# ATU_LC.net
KiCad netlist of a schematic drawn in Altium Designer
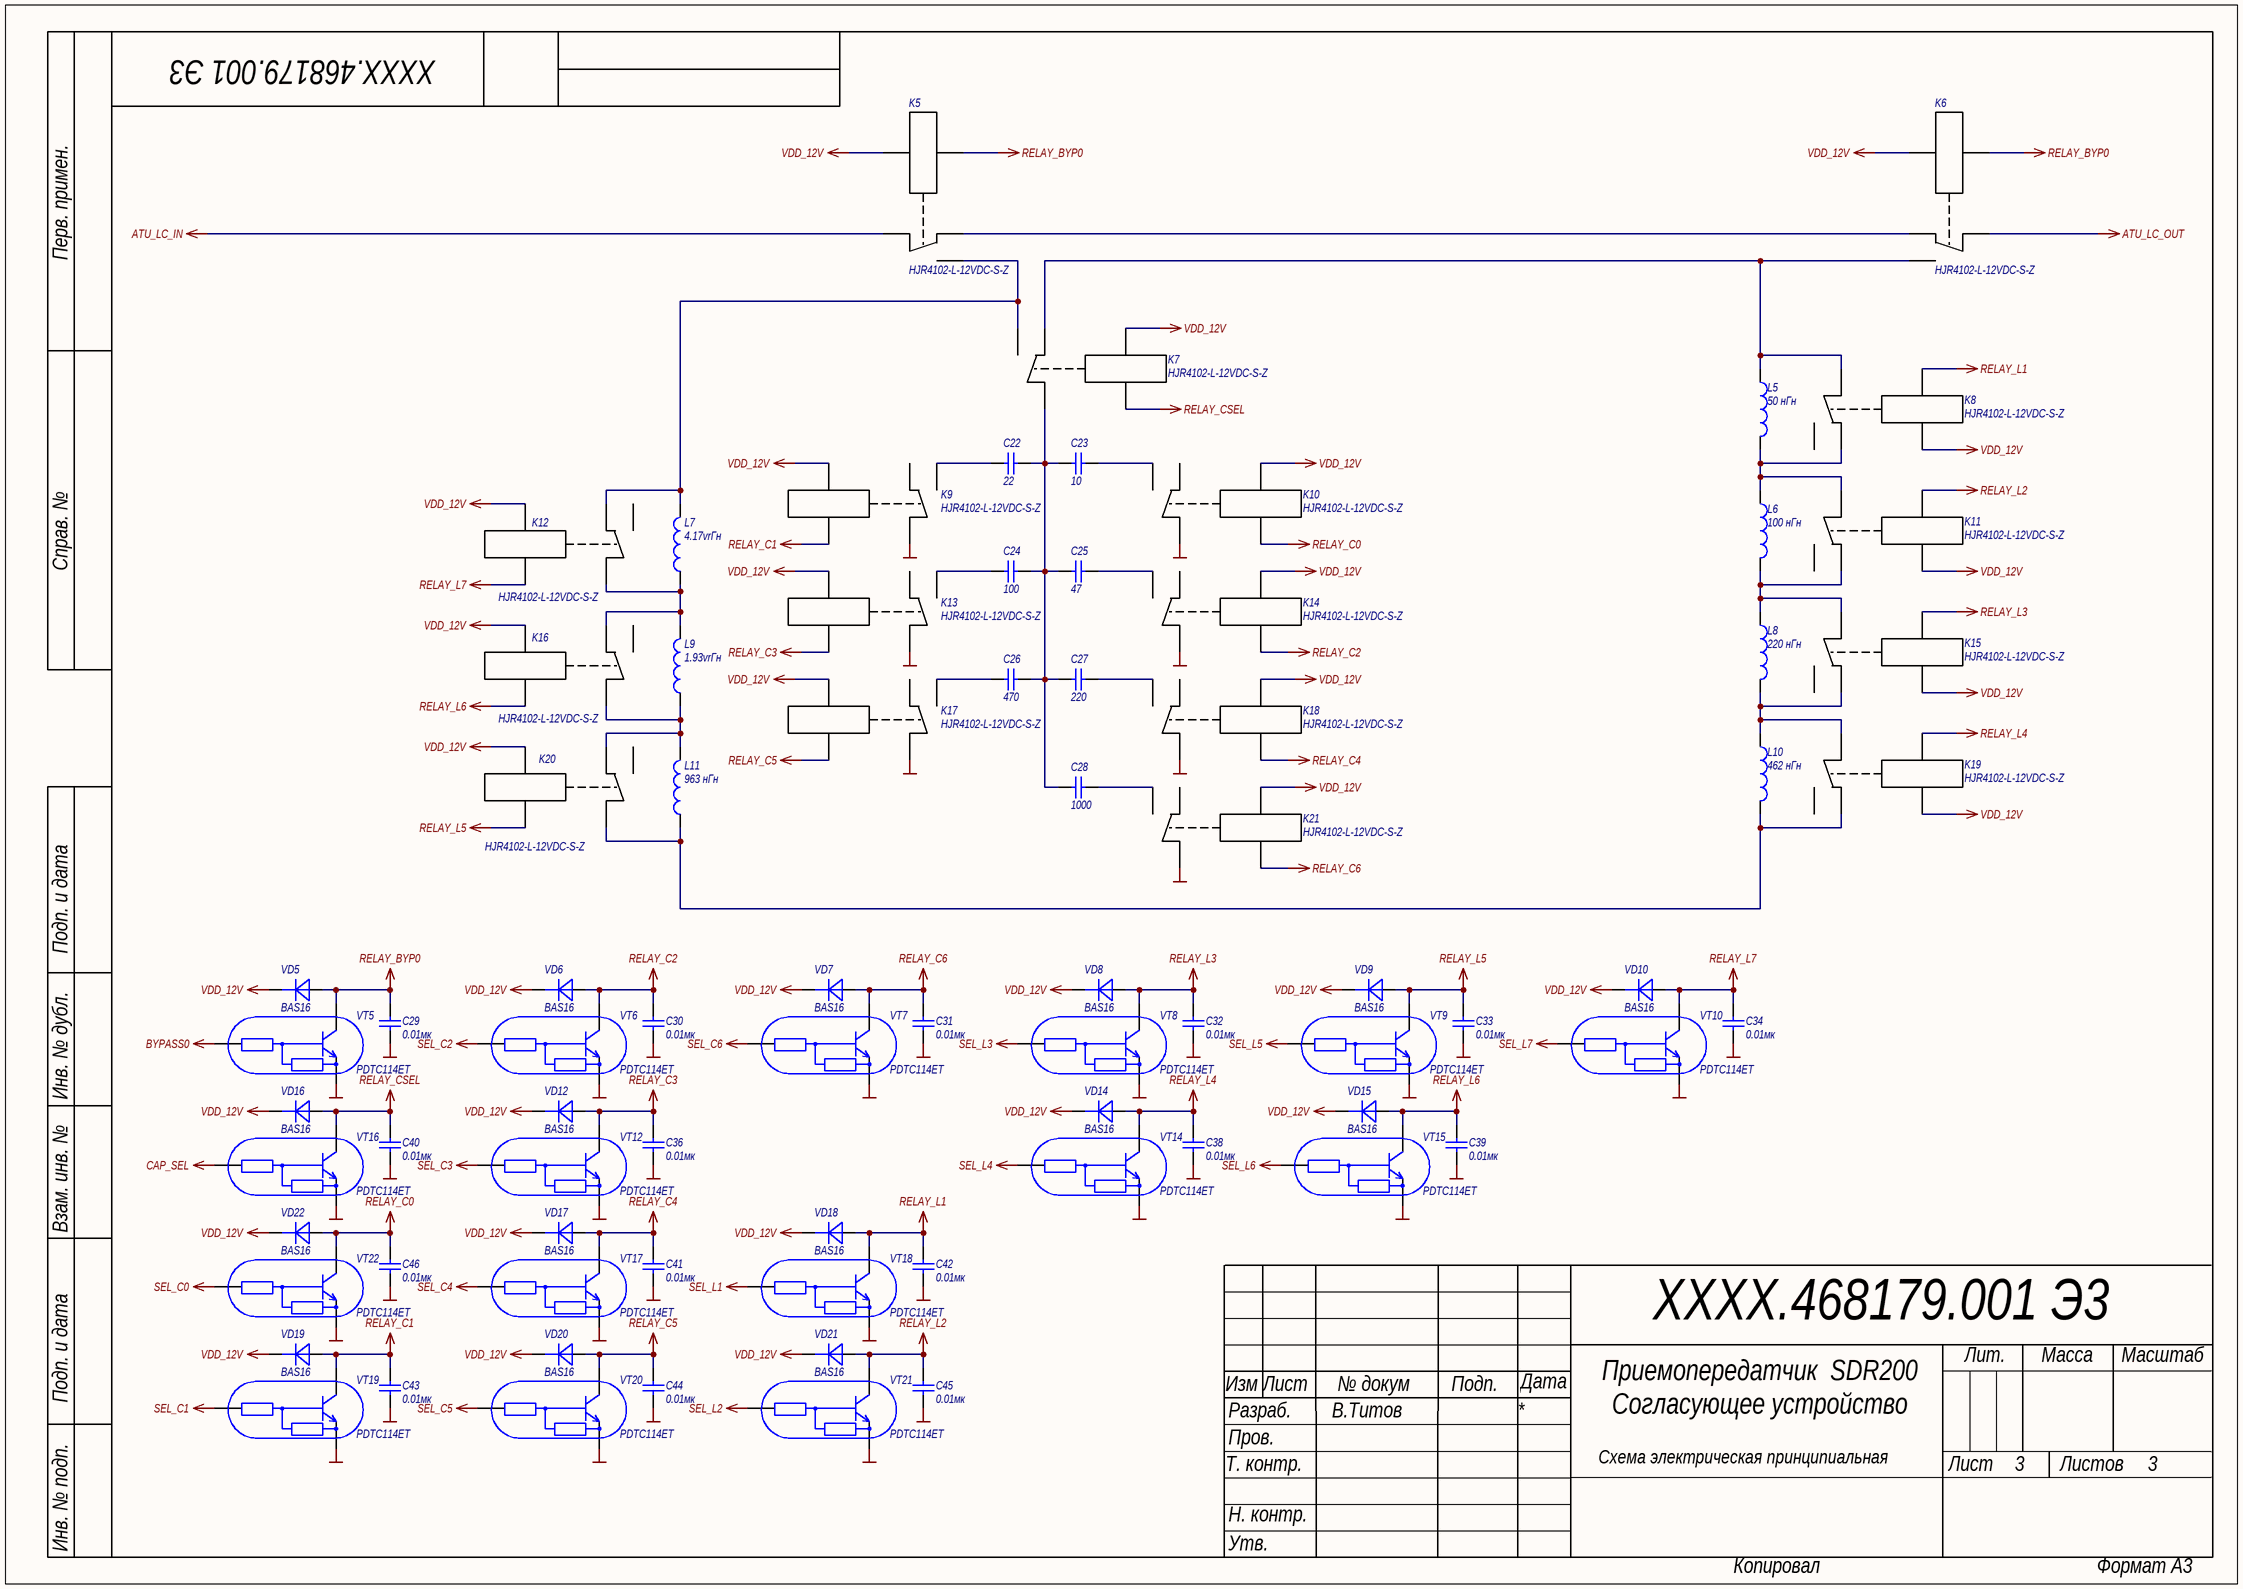
[diagram p0: ATU_LC.SchDoc]

(export (version "E")
  (design (tool "Eeschema 10.0.6"))
  (components
    (comp (ref "C22")
      (value "22")
      (footprint "CAPC3216X19L")
      (description "Кер. ЧИП-конденсатор")
      (fields (field (name "MANUFACTURER") "WALSIN") (field (name "TOLERANCE") "±5%"))
      (libsource (lib "nels_caps") (part "Кер.ЧИП конд. 1206 22пФ NP0 5% 2000В"))
    )
    (comp (ref "C23")
      (value "10")
      (footprint "CAPC3216X19L")
      (description "Кер. ЧИП-конденсатор")
      (fields (field (name "MANUFACTURER") "WALSIN") (field (name "TOLERANCE") "±5%"))
      (libsource (lib "nels_caps") (part "Кер.ЧИП конд. 1206 10пФ NP0 5% 2000В"))
    )
    (comp (ref "C24")
      (value "100")
      (footprint "CAPC3216X19L")
      (description "Кер. ЧИП-конденсатор")
      (fields (field (name "MANUFACTURER") "WALSIN") (field (name "TOLERANCE") "±5%"))
      (libsource (lib "nels_caps") (part "Кер.ЧИП конд. 1206 100пФ NP0 5% 2000В"))
    )
    (comp (ref "C25")
      (value "47")
      (footprint "CAPC3216X19L")
      (description "Кер. ЧИП-конденсатор")
      (fields (field (name "MANUFACTURER") "WALSIN") (field (name "TOLERANCE") "±5%"))
      (libsource (lib "nels_caps") (part "Кер.ЧИП конд. 1206 47пФ NP0 5% 2000В"))
    )
    (comp (ref "C26")
      (value "470")
      (footprint "CAPC3216X19L")
      (description "Кер. ЧИП-конденсатор")
      (fields (field (name "MANUFACTURER") "WALSIN") (field (name "TOLERANCE") "±10%"))
      (libsource (lib "nels_caps") (part "Кер.ЧИП конд. 1206 470пФ NP0 10% 2000В"))
    )
    (comp (ref "C27")
      (value "220")
      (footprint "CAPC3216X19L")
      (description "Кер. ЧИП-конденсатор")
      (fields (field (name "MANUFACTURER") "Johanson") (field (name "TOLERANCE") "±10%"))
      (libsource (lib "nels_caps") (part "Кер.ЧИП конд. 1206 220пФ NP0 5% 2000В"))
    )
    (comp (ref "C28")
      (value "1000")
      (footprint "CAPC3216X19L")
      (description "Кер. ЧИП-конденсатор")
      (fields (field (name "MANUFACTURER") "Johanson") (field (name "TOLERANCE") "±10%"))
      (libsource (lib "nels_caps") (part "Кер.ЧИП конд. 1206 1000пФ X7К 10% 2000В"))
    )
    (comp (ref "C29")
      (value "0.01мк")
      (footprint "CAPC1005X06N")
      (description "Кер. ЧИП-конденсатор")
      (fields (field (name "TOLERANCE") "±20%"))
      (libsource (lib "nels_caps") (part "Кер.ЧИП конд. 0402 0.01мкФ X7R 10%, 50В"))
    )
    (comp (ref "C30")
      (value "0.01мк")
      (footprint "CAPC1005X06N")
      (description "Кер. ЧИП-конденсатор")
      (fields (field (name "TOLERANCE") "±20%"))
      (libsource (lib "nels_caps") (part "Кер.ЧИП конд. 0402 0.01мкФ X7R 10%, 50В"))
    )
    (comp (ref "C31")
      (value "0.01мк")
      (footprint "CAPC1005X06N")
      (description "Кер. ЧИП-конденсатор")
      (fields (field (name "TOLERANCE") "±20%"))
      (libsource (lib "nels_caps") (part "Кер.ЧИП конд. 0402 0.01мкФ X7R 10%, 50В"))
    )
    (comp (ref "C32")
      (value "0.01мк")
      (footprint "CAPC1005X06N")
      (description "Кер. ЧИП-конденсатор")
      (fields (field (name "TOLERANCE") "±20%"))
      (libsource (lib "nels_caps") (part "Кер.ЧИП конд. 0402 0.01мкФ X7R 10%, 50В"))
    )
    (comp (ref "C33")
      (value "0.01мк")
      (footprint "CAPC1005X06N")
      (description "Кер. ЧИП-конденсатор")
      (fields (field (name "TOLERANCE") "±20%"))
      (libsource (lib "nels_caps") (part "Кер.ЧИП конд. 0402 0.01мкФ X7R 10%, 50В"))
    )
    (comp (ref "C34")
      (value "0.01мк")
      (footprint "CAPC1005X06N")
      (description "Кер. ЧИП-конденсатор")
      (fields (field (name "TOLERANCE") "±20%"))
      (libsource (lib "nels_caps") (part "Кер.ЧИП конд. 0402 0.01мкФ X7R 10%, 50В"))
    )
    (comp (ref "C36")
      (value "0.01мк")
      (footprint "CAPC1005X06N")
      (description "Кер. ЧИП-конденсатор")
      (fields (field (name "TOLERANCE") "±20%"))
      (libsource (lib "nels_caps") (part "Кер.ЧИП конд. 0402 0.01мкФ X7R 10%, 50В"))
    )
    (comp (ref "C38")
      (value "0.01мк")
      (footprint "CAPC1005X06N")
      (description "Кер. ЧИП-конденсатор")
      (fields (field (name "TOLERANCE") "±20%"))
      (libsource (lib "nels_caps") (part "Кер.ЧИП конд. 0402 0.01мкФ X7R 10%, 50В"))
    )
    (comp (ref "C39")
      (value "0.01мк")
      (footprint "CAPC1005X06N")
      (description "Кер. ЧИП-конденсатор")
      (fields (field (name "TOLERANCE") "±20%"))
      (libsource (lib "nels_caps") (part "Кер.ЧИП конд. 0402 0.01мкФ X7R 10%, 50В"))
    )
    (comp (ref "C40")
      (value "0.01мк")
      (footprint "CAPC1005X06N")
      (description "Кер. ЧИП-конденсатор")
      (fields (field (name "TOLERANCE") "±20%"))
      (libsource (lib "nels_caps") (part "Кер.ЧИП конд. 0402 0.01мкФ X7R 10%, 50В"))
    )
    (comp (ref "C41")
      (value "0.01мк")
      (footprint "CAPC1005X06N")
      (description "Кер. ЧИП-конденсатор")
      (fields (field (name "TOLERANCE") "±20%"))
      (libsource (lib "nels_caps") (part "Кер.ЧИП конд. 0402 0.01мкФ X7R 10%, 50В"))
    )
    (comp (ref "C42")
      (value "0.01мк")
      (footprint "CAPC1005X06N")
      (description "Кер. ЧИП-конденсатор")
      (fields (field (name "TOLERANCE") "±20%"))
      (libsource (lib "nels_caps") (part "Кер.ЧИП конд. 0402 0.01мкФ X7R 10%, 50В"))
    )
    (comp (ref "C43")
      (value "0.01мк")
      (footprint "CAPC1005X06N")
      (description "Кер. ЧИП-конденсатор")
      (fields (field (name "TOLERANCE") "±20%"))
      (libsource (lib "nels_caps") (part "Кер.ЧИП конд. 0402 0.01мкФ X7R 10%, 50В"))
    )
    (comp (ref "C44")
      (value "0.01мк")
      (footprint "CAPC1005X06N")
      (description "Кер. ЧИП-конденсатор")
      (fields (field (name "TOLERANCE") "±20%"))
      (libsource (lib "nels_caps") (part "Кер.ЧИП конд. 0402 0.01мкФ X7R 10%, 50В"))
    )
    (comp (ref "C45")
      (value "0.01мк")
      (footprint "CAPC1005X06N")
      (description "Кер. ЧИП-конденсатор")
      (fields (field (name "TOLERANCE") "±20%"))
      (libsource (lib "nels_caps") (part "Кер.ЧИП конд. 0402 0.01мкФ X7R 10%, 50В"))
    )
    (comp (ref "C46")
      (value "0.01мк")
      (footprint "CAPC1005X06N")
      (description "Кер. ЧИП-конденсатор")
      (fields (field (name "TOLERANCE") "±20%"))
      (libsource (lib "nels_caps") (part "Кер.ЧИП конд. 0402 0.01мкФ X7R 10%, 50В"))
    )
    (comp (ref "K5")
      (value "HJR4102-L-12VDC-S-Z")
      (footprint "HJR4102")
      (description "Реле 1пер. 12VDC, 1A/240VAC")
      (libsource (lib "nels_other") (part "Реле HJR4102-L-12VDC-S-Z"))
    )
    (comp (ref "K6")
      (value "HJR4102-L-12VDC-S-Z")
      (footprint "HJR4102")
      (description "Реле 1пер. 12VDC, 1A/240VAC")
      (libsource (lib "nels_other") (part "Реле HJR4102-L-12VDC-S-Z"))
    )
    (comp (ref "K7")
      (value "HJR4102-L-12VDC-S-Z")
      (footprint "HJR4102")
      (description "Реле 1пер. 12VDC, 1A/240VAC")
      (libsource (lib "nels_other") (part "Реле HJR4102-L-12VDC-S-Z"))
    )
    (comp (ref "K8")
      (value "HJR4102-L-12VDC-S-Z")
      (footprint "HJR4102")
      (description "Реле 1пер. 12VDC, 1A/240VAC")
      (libsource (lib "nels_other") (part "Реле HJR4102-L-12VDC-S-Z"))
    )
    (comp (ref "K9")
      (value "HJR4102-L-12VDC-S-Z")
      (footprint "HJR4102")
      (description "Реле 1пер. 12VDC, 1A/240VAC")
      (libsource (lib "nels_other") (part "Реле HJR4102-L-12VDC-S-Z"))
    )
    (comp (ref "K10")
      (value "HJR4102-L-12VDC-S-Z")
      (footprint "HJR4102")
      (description "Реле 1пер. 12VDC, 1A/240VAC")
      (libsource (lib "nels_other") (part "Реле HJR4102-L-12VDC-S-Z"))
    )
    (comp (ref "K11")
      (value "HJR4102-L-12VDC-S-Z")
      (footprint "HJR4102")
      (description "Реле 1пер. 12VDC, 1A/240VAC")
      (libsource (lib "nels_other") (part "Реле HJR4102-L-12VDC-S-Z"))
    )
    (comp (ref "K12")
      (value "HJR4102-L-12VDC-S-Z")
      (footprint "HJR4102")
      (description "Реле 1пер. 12VDC, 1A/240VAC")
      (libsource (lib "nels_other") (part "Реле HJR4102-L-12VDC-S-Z"))
    )
    (comp (ref "K13")
      (value "HJR4102-L-12VDC-S-Z")
      (footprint "HJR4102")
      (description "Реле 1пер. 12VDC, 1A/240VAC")
      (libsource (lib "nels_other") (part "Реле HJR4102-L-12VDC-S-Z"))
    )
    (comp (ref "K14")
      (value "HJR4102-L-12VDC-S-Z")
      (footprint "HJR4102")
      (description "Реле 1пер. 12VDC, 1A/240VAC")
      (libsource (lib "nels_other") (part "Реле HJR4102-L-12VDC-S-Z"))
    )
    (comp (ref "K15")
      (value "HJR4102-L-12VDC-S-Z")
      (footprint "HJR4102")
      (description "Реле 1пер. 12VDC, 1A/240VAC")
      (libsource (lib "nels_other") (part "Реле HJR4102-L-12VDC-S-Z"))
    )
    (comp (ref "K16")
      (value "HJR4102-L-12VDC-S-Z")
      (footprint "HJR4102")
      (description "Реле 1пер. 12VDC, 1A/240VAC")
      (libsource (lib "nels_other") (part "Реле HJR4102-L-12VDC-S-Z"))
    )
    (comp (ref "K17")
      (value "HJR4102-L-12VDC-S-Z")
      (footprint "HJR4102")
      (description "Реле 1пер. 12VDC, 1A/240VAC")
      (libsource (lib "nels_other") (part "Реле HJR4102-L-12VDC-S-Z"))
    )
    (comp (ref "K18")
      (value "HJR4102-L-12VDC-S-Z")
      (footprint "HJR4102")
      (description "Реле 1пер. 12VDC, 1A/240VAC")
      (libsource (lib "nels_other") (part "Реле HJR4102-L-12VDC-S-Z"))
    )
    (comp (ref "K19")
      (value "HJR4102-L-12VDC-S-Z")
      (footprint "HJR4102")
      (description "Реле 1пер. 12VDC, 1A/240VAC")
      (libsource (lib "nels_other") (part "Реле HJR4102-L-12VDC-S-Z"))
    )
    (comp (ref "K20")
      (value "HJR4102-L-12VDC-S-Z")
      (footprint "HJR4102")
      (description "Реле 1пер. 12VDC, 1A/240VAC")
      (libsource (lib "nels_other") (part "Реле HJR4102-L-12VDC-S-Z"))
    )
    (comp (ref "K21")
      (value "HJR4102-L-12VDC-S-Z")
      (footprint "HJR4102")
      (description "Реле 1пер. 12VDC, 1A/240VAC")
      (libsource (lib "nels_other") (part "Реле HJR4102-L-12VDC-S-Z"))
    )
    (comp (ref "L5")
      (value "50 нГн")
      (footprint "COIL D4 W3 L3")
      (description "3 витка, диаметр 4мм, длина 3мм, провод 0,5мм")
      (libsource (lib "nels_ind") (part "Индуктивность 50 нГн"))
    )
    (comp (ref "L6")
      (value "100 нГн")
      (footprint "COIL D6.4 W4 L3.5")
      (description "4 витка, диаметр 6мм, длина 3.5мм, провод 0.8мм")
      (libsource (lib "nels_ind") (part "Индуктивность  100 нГн"))
    )
    (comp (ref "L7")
      (value "4.17vrГн")
      (footprint "T68-2x2")
      (description "13 витков на 2 кольцах")
      (libsource (lib "nels_ind") (part "Индуктивность 2XT68-2 4.17vrГн"))
    )
    (comp (ref "L8")
      (value "220 нГн")
      (footprint "COIL D6.4 W7 L6")
      (description "7 витков, диаметр 6мм, длина 6мм, провод 0.8мм")
      (libsource (lib "nels_ind") (part "Индуктивность 220 нГн"))
    )
    (comp (ref "L9")
      (value "1.93vrГн")
      (footprint "T68-2x2")
      (description "13 витков на 2 кольцах")
      (libsource (lib "nels_ind") (part "Индуктивность 2XT68-2 1.93vrГн"))
    )
    (comp (ref "L10")
      (value "462 нГн")
      (footprint "T68-2")
      (description "9 витков")
      (libsource (lib "nels_ind") (part "Индуктивность T68-2 462 нГн"))
    )
    (comp (ref "L11")
      (value "963 нГн")
      (footprint "T68-2")
      (description "13 витков")
      (libsource (lib "nels_ind") (part "Индуктивность T68-2 963 нГн"))
    )
    (comp (ref "VD5")
      (value "BAS16")
      (footprint "SOT23_N")
      (description "High-speed switching diodes")
      (fields (field (name "MANUFACTURER") "Nexperia"))
      (libsource (lib "nels_other") (part "ЧИП диод BAS16"))
    )
    (comp (ref "VD6")
      (value "BAS16")
      (footprint "SOT23_N")
      (description "High-speed switching diodes")
      (fields (field (name "MANUFACTURER") "Nexperia"))
      (libsource (lib "nels_other") (part "ЧИП диод BAS16"))
    )
    (comp (ref "VD7")
      (value "BAS16")
      (footprint "SOT23_N")
      (description "High-speed switching diodes")
      (fields (field (name "MANUFACTURER") "Nexperia"))
      (libsource (lib "nels_other") (part "ЧИП диод BAS16"))
    )
    (comp (ref "VD8")
      (value "BAS16")
      (footprint "SOT23_N")
      (description "High-speed switching diodes")
      (fields (field (name "MANUFACTURER") "Nexperia"))
      (libsource (lib "nels_other") (part "ЧИП диод BAS16"))
    )
    (comp (ref "VD9")
      (value "BAS16")
      (footprint "SOT23_N")
      (description "High-speed switching diodes")
      (fields (field (name "MANUFACTURER") "Nexperia"))
      (libsource (lib "nels_other") (part "ЧИП диод BAS16"))
    )
    (comp (ref "VD10")
      (value "BAS16")
      (footprint "SOT23_N")
      (description "High-speed switching diodes")
      (fields (field (name "MANUFACTURER") "Nexperia"))
      (libsource (lib "nels_other") (part "ЧИП диод BAS16"))
    )
    (comp (ref "VD12")
      (value "BAS16")
      (footprint "SOT23_N")
      (description "High-speed switching diodes")
      (fields (field (name "MANUFACTURER") "Nexperia"))
      (libsource (lib "nels_other") (part "ЧИП диод BAS16"))
    )
    (comp (ref "VD14")
      (value "BAS16")
      (footprint "SOT23_N")
      (description "High-speed switching diodes")
      (fields (field (name "MANUFACTURER") "Nexperia"))
      (libsource (lib "nels_other") (part "ЧИП диод BAS16"))
    )
    (comp (ref "VD15")
      (value "BAS16")
      (footprint "SOT23_N")
      (description "High-speed switching diodes")
      (fields (field (name "MANUFACTURER") "Nexperia"))
      (libsource (lib "nels_other") (part "ЧИП диод BAS16"))
    )
    (comp (ref "VD16")
      (value "BAS16")
      (footprint "SOT23_N")
      (description "High-speed switching diodes")
      (fields (field (name "MANUFACTURER") "Nexperia"))
      (libsource (lib "nels_other") (part "ЧИП диод BAS16"))
    )
    (comp (ref "VD17")
      (value "BAS16")
      (footprint "SOT23_N")
      (description "High-speed switching diodes")
      (fields (field (name "MANUFACTURER") "Nexperia"))
      (libsource (lib "nels_other") (part "ЧИП диод BAS16"))
    )
    (comp (ref "VD18")
      (value "BAS16")
      (footprint "SOT23_N")
      (description "High-speed switching diodes")
      (fields (field (name "MANUFACTURER") "Nexperia"))
      (libsource (lib "nels_other") (part "ЧИП диод BAS16"))
    )
    (comp (ref "VD19")
      (value "BAS16")
      (footprint "SOT23_N")
      (description "High-speed switching diodes")
      (fields (field (name "MANUFACTURER") "Nexperia"))
      (libsource (lib "nels_other") (part "ЧИП диод BAS16"))
    )
    (comp (ref "VD20")
      (value "BAS16")
      (footprint "SOT23_N")
      (description "High-speed switching diodes")
      (fields (field (name "MANUFACTURER") "Nexperia"))
      (libsource (lib "nels_other") (part "ЧИП диод BAS16"))
    )
    (comp (ref "VD21")
      (value "BAS16")
      (footprint "SOT23_N")
      (description "High-speed switching diodes")
      (fields (field (name "MANUFACTURER") "Nexperia"))
      (libsource (lib "nels_other") (part "ЧИП диод BAS16"))
    )
    (comp (ref "VD22")
      (value "BAS16")
      (footprint "SOT23_N")
      (description "High-speed switching diodes")
      (fields (field (name "MANUFACTURER") "Nexperia"))
      (libsource (lib "nels_other") (part "ЧИП диод BAS16"))
    )
    (comp (ref "VT5")
      (value "PDTC114ET")
      (footprint "SOT23_N")
      (description "NPN resistor-equipped transistors;  R1 = 10 k, R2 = 10")
      (libsource (lib "nels_other") (part "ЧИП транзистор PDTC114ET"))
    )
    (comp (ref "VT6")
      (value "PDTC114ET")
      (footprint "SOT23_N")
      (description "NPN resistor-equipped transistors;  R1 = 10 k, R2 = 10")
      (libsource (lib "nels_other") (part "ЧИП транзистор PDTC114ET"))
    )
    (comp (ref "VT7")
      (value "PDTC114ET")
      (footprint "SOT23_N")
      (description "NPN resistor-equipped transistors;  R1 = 10 k, R2 = 10")
      (libsource (lib "nels_other") (part "ЧИП транзистор PDTC114ET"))
    )
    (comp (ref "VT8")
      (value "PDTC114ET")
      (footprint "SOT23_N")
      (description "NPN resistor-equipped transistors;  R1 = 10 k, R2 = 10")
      (libsource (lib "nels_other") (part "ЧИП транзистор PDTC114ET"))
    )
    (comp (ref "VT9")
      (value "PDTC114ET")
      (footprint "SOT23_N")
      (description "NPN resistor-equipped transistors;  R1 = 10 k, R2 = 10")
      (libsource (lib "nels_other") (part "ЧИП транзистор PDTC114ET"))
    )
    (comp (ref "VT10")
      (value "PDTC114ET")
      (footprint "SOT23_N")
      (description "NPN resistor-equipped transistors;  R1 = 10 k, R2 = 10")
      (libsource (lib "nels_other") (part "ЧИП транзистор PDTC114ET"))
    )
    (comp (ref "VT12")
      (value "PDTC114ET")
      (footprint "SOT23_N")
      (description "NPN resistor-equipped transistors;  R1 = 10 k, R2 = 10")
      (libsource (lib "nels_other") (part "ЧИП транзистор PDTC114ET"))
    )
    (comp (ref "VT14")
      (value "PDTC114ET")
      (footprint "SOT23_N")
      (description "NPN resistor-equipped transistors;  R1 = 10 k, R2 = 10")
      (libsource (lib "nels_other") (part "ЧИП транзистор PDTC114ET"))
    )
    (comp (ref "VT15")
      (value "PDTC114ET")
      (footprint "SOT23_N")
      (description "NPN resistor-equipped transistors;  R1 = 10 k, R2 = 10")
      (libsource (lib "nels_other") (part "ЧИП транзистор PDTC114ET"))
    )
    (comp (ref "VT16")
      (value "PDTC114ET")
      (footprint "SOT23_N")
      (description "NPN resistor-equipped transistors;  R1 = 10 k, R2 = 10")
      (libsource (lib "nels_other") (part "ЧИП транзистор PDTC114ET"))
    )
    (comp (ref "VT17")
      (value "PDTC114ET")
      (footprint "SOT23_N")
      (description "NPN resistor-equipped transistors;  R1 = 10 k, R2 = 10")
      (libsource (lib "nels_other") (part "ЧИП транзистор PDTC114ET"))
    )
    (comp (ref "VT18")
      (value "PDTC114ET")
      (footprint "SOT23_N")
      (description "NPN resistor-equipped transistors;  R1 = 10 k, R2 = 10")
      (libsource (lib "nels_other") (part "ЧИП транзистор PDTC114ET"))
    )
    (comp (ref "VT19")
      (value "PDTC114ET")
      (footprint "SOT23_N")
      (description "NPN resistor-equipped transistors;  R1 = 10 k, R2 = 10")
      (libsource (lib "nels_other") (part "ЧИП транзистор PDTC114ET"))
    )
    (comp (ref "VT20")
      (value "PDTC114ET")
      (footprint "SOT23_N")
      (description "NPN resistor-equipped transistors;  R1 = 10 k, R2 = 10")
      (libsource (lib "nels_other") (part "ЧИП транзистор PDTC114ET"))
    )
    (comp (ref "VT21")
      (value "PDTC114ET")
      (footprint "SOT23_N")
      (description "NPN resistor-equipped transistors;  R1 = 10 k, R2 = 10")
      (libsource (lib "nels_other") (part "ЧИП транзистор PDTC114ET"))
    )
    (comp (ref "VT22")
      (value "PDTC114ET")
      (footprint "SOT23_N")
      (description "NPN resistor-equipped transistors;  R1 = 10 k, R2 = 10")
      (libsource (lib "nels_other") (part "ЧИП транзистор PDTC114ET"))
    )
  )
  (nets
    (net (code "1") (name "ATU_LC_IN") (class "Default") (node (ref "K5") (pin "1") (pintype "passive")))
    (net (code "2") (name "ATU_LC_OUT") (class "Default") (node (ref "K6") (pin "1") (pintype "passive")))
    (net (code "3") (name "BYPASS0") (class "Default")
      (node (ref "VT5") (pin "1") (pinfunction "B_1") (pintype "passive"))
    )
    (net (code "4") (name "CAP_SEL") (class "Default")
      (node (ref "VT16") (pin "1") (pinfunction "B_1") (pintype "passive"))
    )
    (net (code "5") (name "GND") (class "Default")
      (node (ref "C29") (pin "1") (pinfunction "1_1") (pintype "passive"))
      (node (ref "C30") (pin "1") (pinfunction "1_1") (pintype "passive"))
      (node (ref "C31") (pin "1") (pinfunction "1_1") (pintype "passive"))
      (node (ref "C32") (pin "1") (pinfunction "1_1") (pintype "passive"))
      (node (ref "C33") (pin "1") (pinfunction "1_1") (pintype "passive"))
      (node (ref "C34") (pin "1") (pinfunction "1_1") (pintype "passive"))
      (node (ref "C36") (pin "1") (pinfunction "1_1") (pintype "passive"))
      (node (ref "C38") (pin "1") (pinfunction "1_1") (pintype "passive"))
      (node (ref "C39") (pin "1") (pinfunction "1_1") (pintype "passive"))
      (node (ref "C40") (pin "1") (pinfunction "1_1") (pintype "passive"))
      (node (ref "C41") (pin "1") (pinfunction "1_1") (pintype "passive"))
      (node (ref "C42") (pin "1") (pinfunction "1_1") (pintype "passive"))
      (node (ref "C43") (pin "1") (pinfunction "1_1") (pintype "passive"))
      (node (ref "C44") (pin "1") (pinfunction "1_1") (pintype "passive"))
      (node (ref "C45") (pin "1") (pinfunction "1_1") (pintype "passive"))
      (node (ref "C46") (pin "1") (pinfunction "1_1") (pintype "passive"))
      (node (ref "K10") (pin "1") (pintype "passive"))
      (node (ref "K13") (pin "1") (pintype "passive"))
      (node (ref "K14") (pin "1") (pintype "passive"))
      (node (ref "K17") (pin "1") (pintype "passive"))
      (node (ref "K18") (pin "1") (pintype "passive"))
      (node (ref "K21") (pin "1") (pintype "passive"))
      (node (ref "K9") (pin "1") (pintype "passive"))
      (node (ref "VT10") (pin "2") (pinfunction "E_2") (pintype "passive"))
      (node (ref "VT12") (pin "2") (pinfunction "E_2") (pintype "passive"))
      (node (ref "VT14") (pin "2") (pinfunction "E_2") (pintype "passive"))
      (node (ref "VT15") (pin "2") (pinfunction "E_2") (pintype "passive"))
      (node (ref "VT16") (pin "2") (pinfunction "E_2") (pintype "passive"))
      (node (ref "VT17") (pin "2") (pinfunction "E_2") (pintype "passive"))
      (node (ref "VT18") (pin "2") (pinfunction "E_2") (pintype "passive"))
      (node (ref "VT19") (pin "2") (pinfunction "E_2") (pintype "passive"))
      (node (ref "VT20") (pin "2") (pinfunction "E_2") (pintype "passive"))
      (node (ref "VT21") (pin "2") (pinfunction "E_2") (pintype "passive"))
      (node (ref "VT22") (pin "2") (pinfunction "E_2") (pintype "passive"))
      (node (ref "VT5") (pin "2") (pinfunction "E_2") (pintype "passive"))
      (node (ref "VT6") (pin "2") (pinfunction "E_2") (pintype "passive"))
      (node (ref "VT7") (pin "2") (pinfunction "E_2") (pintype "passive"))
      (node (ref "VT8") (pin "2") (pinfunction "E_2") (pintype "passive"))
      (node (ref "VT9") (pin "2") (pinfunction "E_2") (pintype "passive"))
    )
    (net (code "6") (name "Net-(C22-Pad1)") (class "Default")
      (node (ref "C22") (pin "1") (pinfunction "1_1") (pintype "passive"))
      (node (ref "C23") (pin "2") (pinfunction "2_2") (pintype "passive"))
      (node (ref "C24") (pin "1") (pinfunction "1_1") (pintype "passive"))
      (node (ref "C25") (pin "2") (pinfunction "2_2") (pintype "passive"))
      (node (ref "C26") (pin "1") (pinfunction "1_1") (pintype "passive"))
      (node (ref "C27") (pin "2") (pinfunction "2_2") (pintype "passive"))
      (node (ref "C28") (pin "2") (pinfunction "2_2") (pintype "passive"))
      (node (ref "K7") (pin "1") (pintype "passive"))
    )
    (net (code "7") (name "Net-(C22-Pad2)") (class "Default")
      (node (ref "C22") (pin "2") (pinfunction "2_2") (pintype "passive"))
      (node (ref "K9") (pin "6") (pintype "passive"))
    )
    (net (code "8") (name "Net-(C23-Pad1)") (class "Default")
      (node (ref "C23") (pin "1") (pinfunction "1_1") (pintype "passive"))
      (node (ref "K10") (pin "6") (pintype "passive"))
    )
    (net (code "9") (name "Net-(C24-Pad2)") (class "Default")
      (node (ref "C24") (pin "2") (pinfunction "2_2") (pintype "passive"))
      (node (ref "K13") (pin "6") (pintype "passive"))
    )
    (net (code "10") (name "Net-(C25-Pad1)") (class "Default")
      (node (ref "C25") (pin "1") (pinfunction "1_1") (pintype "passive"))
      (node (ref "K14") (pin "6") (pintype "passive"))
    )
    (net (code "11") (name "Net-(C26-Pad2)") (class "Default")
      (node (ref "C26") (pin "2") (pinfunction "2_2") (pintype "passive"))
      (node (ref "K17") (pin "6") (pintype "passive"))
    )
    (net (code "12") (name "Net-(C27-Pad1)") (class "Default")
      (node (ref "C27") (pin "1") (pinfunction "1_1") (pintype "passive"))
      (node (ref "K18") (pin "6") (pintype "passive"))
    )
    (net (code "13") (name "Net-(C28-Pad1)") (class "Default")
      (node (ref "C28") (pin "1") (pinfunction "1_1") (pintype "passive"))
      (node (ref "K21") (pin "6") (pintype "passive"))
    )
    (net (code "14") (name "Net-(K5-Pad7)") (class "Default")
      (node (ref "K5") (pin "7") (pintype "passive"))
      (node (ref "K6") (pin "7") (pintype "passive"))
    )
    (net (code "15") (name "Net-(K6-Pad6)") (class "Default")
      (node (ref "K6") (pin "6") (pintype "passive"))
      (node (ref "K7") (pin "7") (pintype "passive"))
      (node (ref "K8") (pin "1") (pintype "passive"))
      (node (ref "L5") (pin "1") (pinfunction "1_1") (pintype "passive"))
    )
    (net (code "16") (name "Net-(K11-Pad1)") (class "Default")
      (node (ref "K11") (pin "1") (pintype "passive"))
      (node (ref "K8") (pin "7") (pintype "passive"))
      (node (ref "L5") (pin "2") (pinfunction "2_2") (pintype "passive"))
      (node (ref "L6") (pin "1") (pinfunction "1_1") (pintype "passive"))
    )
    (net (code "17") (name "Net-(K11-Pad7)") (class "Default")
      (node (ref "K11") (pin "7") (pintype "passive"))
      (node (ref "K15") (pin "1") (pintype "passive"))
      (node (ref "L6") (pin "2") (pinfunction "2_2") (pintype "passive"))
      (node (ref "L8") (pin "1") (pinfunction "1_1") (pintype "passive"))
    )
    (net (code "18") (name "Net-(K12-Pad1)") (class "Default")
      (node (ref "K12") (pin "1") (pintype "passive"))
      (node (ref "K16") (pin "7") (pintype "passive"))
      (node (ref "L7") (pin "1") (pinfunction "1_1") (pintype "passive"))
      (node (ref "L9") (pin "2") (pinfunction "2_2") (pintype "passive"))
    )
    (net (code "19") (name "Net-(K12-Pad7)") (class "Default")
      (node (ref "K12") (pin "7") (pintype "passive"))
      (node (ref "K5") (pin "6") (pintype "passive"))
      (node (ref "K7") (pin "6") (pintype "passive"))
      (node (ref "L7") (pin "2") (pinfunction "2_2") (pintype "passive"))
    )
    (net (code "20") (name "Net-(K15-Pad7)") (class "Default")
      (node (ref "K15") (pin "7") (pintype "passive"))
      (node (ref "K19") (pin "1") (pintype "passive"))
      (node (ref "L10") (pin "1") (pinfunction "1_1") (pintype "passive"))
      (node (ref "L8") (pin "2") (pinfunction "2_2") (pintype "passive"))
    )
    (net (code "21") (name "Net-(K16-Pad1)") (class "Default")
      (node (ref "K16") (pin "1") (pintype "passive"))
      (node (ref "K20") (pin "7") (pintype "passive"))
      (node (ref "L11") (pin "2") (pinfunction "2_2") (pintype "passive"))
      (node (ref "L9") (pin "1") (pinfunction "1_1") (pintype "passive"))
    )
    (net (code "22") (name "Net-(K19-Pad7)") (class "Default")
      (node (ref "K19") (pin "7") (pintype "passive"))
      (node (ref "K20") (pin "1") (pintype "passive"))
      (node (ref "L10") (pin "2") (pinfunction "2_2") (pintype "passive"))
      (node (ref "L11") (pin "1") (pinfunction "1_1") (pintype "passive"))
    )
    (net (code "23") (name "RELAY_BYP0") (class "Default")
      (node (ref "C29") (pin "2") (pinfunction "2_2") (pintype "passive"))
      (node (ref "K5") (pin "5") (pintype "passive"))
      (node (ref "K6") (pin "8") (pintype "passive"))
      (node (ref "VD5") (pin "1") (pinfunction "A_1") (pintype "passive"))
      (node (ref "VT5") (pin "3") (pinfunction "C_3") (pintype "passive"))
    )
    (net (code "24") (name "RELAY_C0") (class "Default")
      (node (ref "C46") (pin "2") (pinfunction "2_2") (pintype "passive"))
      (node (ref "K10") (pin "8") (pintype "passive"))
      (node (ref "VD22") (pin "1") (pinfunction "A_1") (pintype "passive"))
      (node (ref "VT22") (pin "3") (pinfunction "C_3") (pintype "passive"))
    )
    (net (code "25") (name "RELAY_C1") (class "Default")
      (node (ref "C43") (pin "2") (pinfunction "2_2") (pintype "passive"))
      (node (ref "K9") (pin "8") (pintype "passive"))
      (node (ref "VD19") (pin "1") (pinfunction "A_1") (pintype "passive"))
      (node (ref "VT19") (pin "3") (pinfunction "C_3") (pintype "passive"))
    )
    (net (code "26") (name "RELAY_C2") (class "Default")
      (node (ref "C30") (pin "2") (pinfunction "2_2") (pintype "passive"))
      (node (ref "K14") (pin "8") (pintype "passive"))
      (node (ref "VD6") (pin "1") (pinfunction "A_1") (pintype "passive"))
      (node (ref "VT6") (pin "3") (pinfunction "C_3") (pintype "passive"))
    )
    (net (code "27") (name "RELAY_C3") (class "Default")
      (node (ref "C36") (pin "2") (pinfunction "2_2") (pintype "passive"))
      (node (ref "K13") (pin "8") (pintype "passive"))
      (node (ref "VD12") (pin "1") (pinfunction "A_1") (pintype "passive"))
      (node (ref "VT12") (pin "3") (pinfunction "C_3") (pintype "passive"))
    )
    (net (code "28") (name "RELAY_C4") (class "Default")
      (node (ref "C41") (pin "2") (pinfunction "2_2") (pintype "passive"))
      (node (ref "K18") (pin "8") (pintype "passive"))
      (node (ref "VD17") (pin "1") (pinfunction "A_1") (pintype "passive"))
      (node (ref "VT17") (pin "3") (pinfunction "C_3") (pintype "passive"))
    )
    (net (code "29") (name "RELAY_C5") (class "Default")
      (node (ref "C44") (pin "2") (pinfunction "2_2") (pintype "passive"))
      (node (ref "K17") (pin "8") (pintype "passive"))
      (node (ref "VD20") (pin "1") (pinfunction "A_1") (pintype "passive"))
      (node (ref "VT20") (pin "3") (pinfunction "C_3") (pintype "passive"))
    )
    (net (code "30") (name "RELAY_C6") (class "Default")
      (node (ref "C31") (pin "2") (pinfunction "2_2") (pintype "passive"))
      (node (ref "K21") (pin "8") (pintype "passive"))
      (node (ref "VD7") (pin "1") (pinfunction "A_1") (pintype "passive"))
      (node (ref "VT7") (pin "3") (pinfunction "C_3") (pintype "passive"))
    )
    (net (code "31") (name "RELAY_CSEL") (class "Default")
      (node (ref "C40") (pin "2") (pinfunction "2_2") (pintype "passive"))
      (node (ref "K7") (pin "8") (pintype "passive"))
      (node (ref "VD16") (pin "1") (pinfunction "A_1") (pintype "passive"))
      (node (ref "VT16") (pin "3") (pinfunction "C_3") (pintype "passive"))
    )
    (net (code "32") (name "RELAY_L1") (class "Default")
      (node (ref "C42") (pin "2") (pinfunction "2_2") (pintype "passive"))
      (node (ref "K8") (pin "8") (pintype "passive"))
      (node (ref "VD18") (pin "1") (pinfunction "A_1") (pintype "passive"))
      (node (ref "VT18") (pin "3") (pinfunction "C_3") (pintype "passive"))
    )
    (net (code "33") (name "RELAY_L2") (class "Default")
      (node (ref "C45") (pin "2") (pinfunction "2_2") (pintype "passive"))
      (node (ref "K11") (pin "8") (pintype "passive"))
      (node (ref "VD21") (pin "1") (pinfunction "A_1") (pintype "passive"))
      (node (ref "VT21") (pin "3") (pinfunction "C_3") (pintype "passive"))
    )
    (net (code "34") (name "RELAY_L3") (class "Default")
      (node (ref "C32") (pin "2") (pinfunction "2_2") (pintype "passive"))
      (node (ref "K15") (pin "8") (pintype "passive"))
      (node (ref "VD8") (pin "1") (pinfunction "A_1") (pintype "passive"))
      (node (ref "VT8") (pin "3") (pinfunction "C_3") (pintype "passive"))
    )
    (net (code "35") (name "RELAY_L4") (class "Default")
      (node (ref "C38") (pin "2") (pinfunction "2_2") (pintype "passive"))
      (node (ref "K19") (pin "8") (pintype "passive"))
      (node (ref "VD14") (pin "1") (pinfunction "A_1") (pintype "passive"))
      (node (ref "VT14") (pin "3") (pinfunction "C_3") (pintype "passive"))
    )
    (net (code "36") (name "RELAY_L5") (class "Default")
      (node (ref "C33") (pin "2") (pinfunction "2_2") (pintype "passive"))
      (node (ref "K20") (pin "8") (pintype "passive"))
      (node (ref "VD9") (pin "1") (pinfunction "A_1") (pintype "passive"))
      (node (ref "VT9") (pin "3") (pinfunction "C_3") (pintype "passive"))
    )
    (net (code "37") (name "RELAY_L6") (class "Default")
      (node (ref "C39") (pin "2") (pinfunction "2_2") (pintype "passive"))
      (node (ref "K16") (pin "8") (pintype "passive"))
      (node (ref "VD15") (pin "1") (pinfunction "A_1") (pintype "passive"))
      (node (ref "VT15") (pin "3") (pinfunction "C_3") (pintype "passive"))
    )
    (net (code "38") (name "RELAY_L7") (class "Default")
      (node (ref "C34") (pin "2") (pinfunction "2_2") (pintype "passive"))
      (node (ref "K12") (pin "8") (pintype "passive"))
      (node (ref "VD10") (pin "1") (pinfunction "A_1") (pintype "passive"))
      (node (ref "VT10") (pin "3") (pinfunction "C_3") (pintype "passive"))
    )
    (net (code "39") (name "SEL_C0") (class "Default")
      (node (ref "VT22") (pin "1") (pinfunction "B_1") (pintype "passive"))
    )
    (net (code "40") (name "SEL_C1") (class "Default")
      (node (ref "VT19") (pin "1") (pinfunction "B_1") (pintype "passive"))
    )
    (net (code "41") (name "SEL_C2") (class "Default")
      (node (ref "VT6") (pin "1") (pinfunction "B_1") (pintype "passive"))
    )
    (net (code "42") (name "SEL_C3") (class "Default")
      (node (ref "VT12") (pin "1") (pinfunction "B_1") (pintype "passive"))
    )
    (net (code "43") (name "SEL_C4") (class "Default")
      (node (ref "VT17") (pin "1") (pinfunction "B_1") (pintype "passive"))
    )
    (net (code "44") (name "SEL_C5") (class "Default")
      (node (ref "VT20") (pin "1") (pinfunction "B_1") (pintype "passive"))
    )
    (net (code "45") (name "SEL_C6") (class "Default")
      (node (ref "VT7") (pin "1") (pinfunction "B_1") (pintype "passive"))
    )
    (net (code "46") (name "SEL_L1") (class "Default")
      (node (ref "VT18") (pin "1") (pinfunction "B_1") (pintype "passive"))
    )
    (net (code "47") (name "SEL_L2") (class "Default")
      (node (ref "VT21") (pin "1") (pinfunction "B_1") (pintype "passive"))
    )
    (net (code "48") (name "SEL_L3") (class "Default")
      (node (ref "VT8") (pin "1") (pinfunction "B_1") (pintype "passive"))
    )
    (net (code "49") (name "SEL_L4") (class "Default")
      (node (ref "VT14") (pin "1") (pinfunction "B_1") (pintype "passive"))
    )
    (net (code "50") (name "SEL_L5") (class "Default")
      (node (ref "VT9") (pin "1") (pinfunction "B_1") (pintype "passive"))
    )
    (net (code "51") (name "SEL_L6") (class "Default")
      (node (ref "VT15") (pin "1") (pinfunction "B_1") (pintype "passive"))
    )
    (net (code "52") (name "SEL_L7") (class "Default")
      (node (ref "VT10") (pin "1") (pinfunction "B_1") (pintype "passive"))
    )
    (net (code "53") (name "VDD_12V") (class "Default")
      (node (ref "K10") (pin "5") (pintype "passive"))
      (node (ref "K11") (pin "5") (pintype "passive"))
      (node (ref "K12") (pin "5") (pintype "passive"))
      (node (ref "K13") (pin "5") (pintype "passive"))
      (node (ref "K14") (pin "5") (pintype "passive"))
      (node (ref "K15") (pin "5") (pintype "passive"))
      (node (ref "K16") (pin "5") (pintype "passive"))
      (node (ref "K17") (pin "5") (pintype "passive"))
      (node (ref "K18") (pin "5") (pintype "passive"))
      (node (ref "K19") (pin "5") (pintype "passive"))
      (node (ref "K20") (pin "5") (pintype "passive"))
      (node (ref "K21") (pin "5") (pintype "passive"))
      (node (ref "K5") (pin "8") (pintype "passive"))
      (node (ref "K6") (pin "5") (pintype "passive"))
      (node (ref "K7") (pin "5") (pintype "passive"))
      (node (ref "K8") (pin "5") (pintype "passive"))
      (node (ref "K9") (pin "5") (pintype "passive"))
      (node (ref "VD10") (pin "3") (pinfunction "K_3") (pintype "passive"))
      (node (ref "VD12") (pin "3") (pinfunction "K_3") (pintype "passive"))
      (node (ref "VD14") (pin "3") (pinfunction "K_3") (pintype "passive"))
      (node (ref "VD15") (pin "3") (pinfunction "K_3") (pintype "passive"))
      (node (ref "VD16") (pin "3") (pinfunction "K_3") (pintype "passive"))
      (node (ref "VD17") (pin "3") (pinfunction "K_3") (pintype "passive"))
      (node (ref "VD18") (pin "3") (pinfunction "K_3") (pintype "passive"))
      (node (ref "VD19") (pin "3") (pinfunction "K_3") (pintype "passive"))
      (node (ref "VD20") (pin "3") (pinfunction "K_3") (pintype "passive"))
      (node (ref "VD21") (pin "3") (pinfunction "K_3") (pintype "passive"))
      (node (ref "VD22") (pin "3") (pinfunction "K_3") (pintype "passive"))
      (node (ref "VD5") (pin "3") (pinfunction "K_3") (pintype "passive"))
      (node (ref "VD6") (pin "3") (pinfunction "K_3") (pintype "passive"))
      (node (ref "VD7") (pin "3") (pinfunction "K_3") (pintype "passive"))
      (node (ref "VD8") (pin "3") (pinfunction "K_3") (pintype "passive"))
      (node (ref "VD9") (pin "3") (pinfunction "K_3") (pintype "passive"))
    )
    (net (code "54") (name "unconnected-(K8-Pad6)") (class "Default")
      (node (ref "K8") (pin "6") (pintype "passive"))
    )
    (net (code "55") (name "unconnected-(K9-Pad7)") (class "Default")
      (node (ref "K9") (pin "7") (pintype "passive"))
    )
    (net (code "56") (name "unconnected-(K10-Pad7)") (class "Default")
      (node (ref "K10") (pin "7") (pintype "passive"))
    )
    (net (code "57") (name "unconnected-(K11-Pad6)") (class "Default")
      (node (ref "K11") (pin "6") (pintype "passive"))
    )
    (net (code "58") (name "unconnected-(K12-Pad6)") (class "Default")
      (node (ref "K12") (pin "6") (pintype "passive"))
    )
    (net (code "59") (name "unconnected-(K13-Pad7)") (class "Default")
      (node (ref "K13") (pin "7") (pintype "passive"))
    )
    (net (code "60") (name "unconnected-(K14-Pad7)") (class "Default")
      (node (ref "K14") (pin "7") (pintype "passive"))
    )
    (net (code "61") (name "unconnected-(K15-Pad6)") (class "Default")
      (node (ref "K15") (pin "6") (pintype "passive"))
    )
    (net (code "62") (name "unconnected-(K16-Pad6)") (class "Default")
      (node (ref "K16") (pin "6") (pintype "passive"))
    )
    (net (code "63") (name "unconnected-(K17-Pad7)") (class "Default")
      (node (ref "K17") (pin "7") (pintype "passive"))
    )
    (net (code "64") (name "unconnected-(K18-Pad7)") (class "Default")
      (node (ref "K18") (pin "7") (pintype "passive"))
    )
    (net (code "65") (name "unconnected-(K19-Pad6)") (class "Default")
      (node (ref "K19") (pin "6") (pintype "passive"))
    )
    (net (code "66") (name "unconnected-(K20-Pad6)") (class "Default")
      (node (ref "K20") (pin "6") (pintype "passive"))
    )
    (net (code "67") (name "unconnected-(K21-Pad7)") (class "Default")
      (node (ref "K21") (pin "7") (pintype "passive"))
    )
  )
)
